# Simple-Temperature-Controller.net
KiCad netlist of a schematic drawn in EAGLE
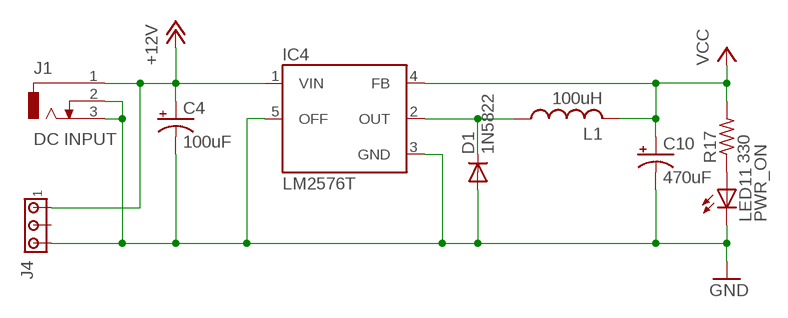
[diagram p0: schematic, sheet 1]
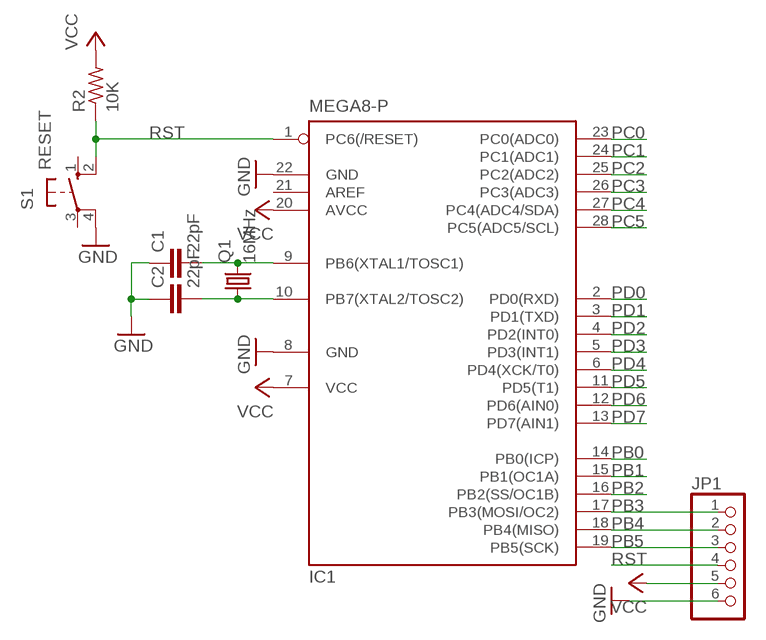
[diagram p1: schematic, sheet 2]
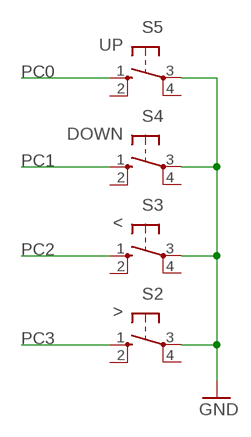
[diagram p2: schematic, sheet 3]
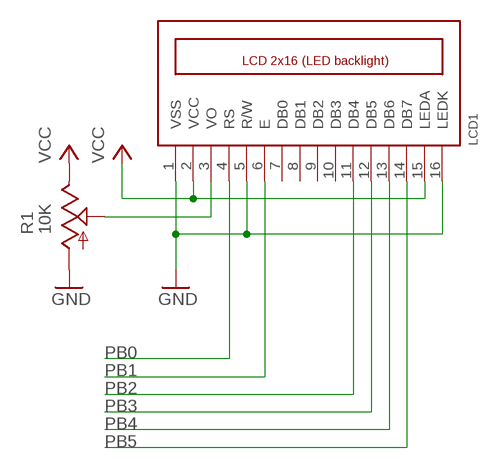
[diagram p3: schematic, sheet 4]
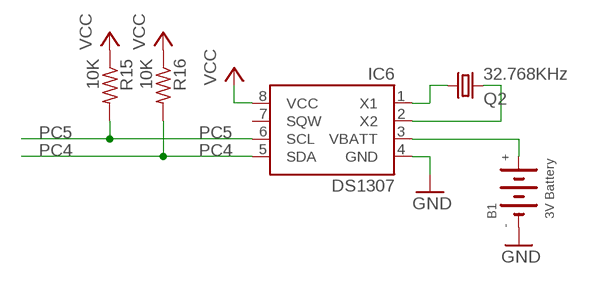
[diagram p4: schematic, sheet 5]
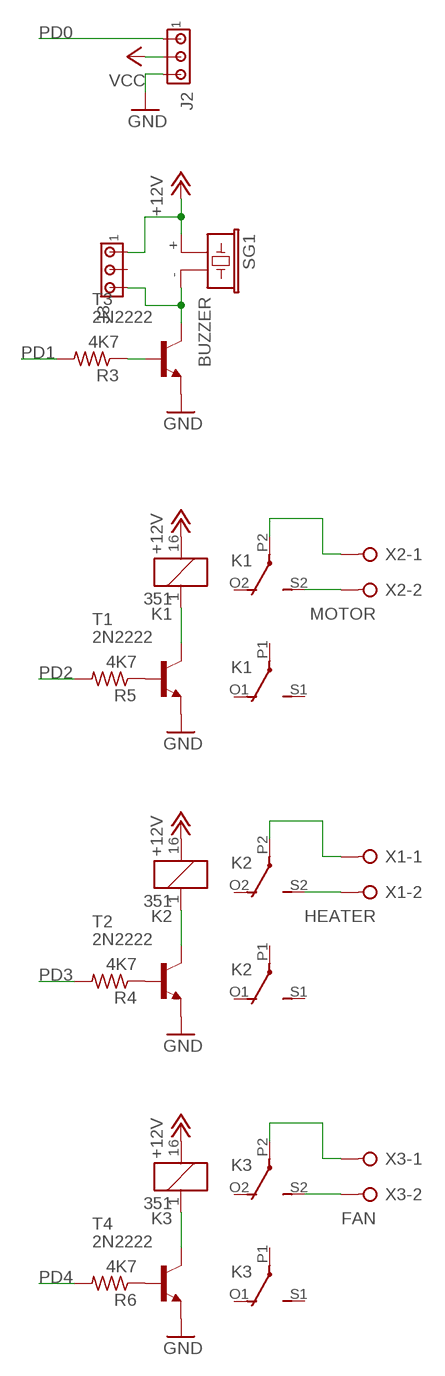
[diagram p5: schematic, sheet 6]

(export (version "E")
  (design (tool "Eeschema 10.0.6"))
  (components
    (comp (ref "C4")
      (value "100uF")
      (footprint "eagle-import:E2,5-6")
      (libsource (lib "eagle-import") (part "CPOL-USE2.5-6"))
    )
    (comp (ref "C10")
      (value "470uF")
      (footprint "eagle-import:E3,5-8")
      (libsource (lib "eagle-import") (part "CPOL-USE3.5-8"))
    )
    (comp (ref "D1")
      (value "1N5822")
      (footprint "eagle-import:DO201-15")
      (libsource (lib "eagle-import") (part "1N5400"))
    )
    (comp (ref "IC4")
      (value "LM2576T")
      (footprint "eagle-import:TO220-5")
      (libsource (lib "eagle-import") (part "LM2576T"))
    )
    (comp (ref "J1")
      (value "DC INPUT")
      (footprint "eagle-import:DCJ0202")
      (libsource (lib "eagle-import") (part "DCJ0202"))
    )
    (comp (ref "J4")
      (value "MTA03-100")
      (footprint "eagle-import:10X03MTA")
      (libsource (lib "eagle-import") (part "MTA03-100"))
    )
    (comp (ref "L1")
      (value "100uH")
      (footprint "eagle-import:TJ3-U2")
      (libsource (lib "eagle-import") (part "L-USTJ3-U2"))
    )
    (comp (ref "LED11")
      (value "PWR_ON")
      (footprint "eagle-import:LED3MM")
      (libsource (lib "eagle-import") (part "LED3MM"))
    )
    (comp (ref "R17")
      (value "330")
      (footprint "eagle-import:0207_10")
      (libsource (lib "eagle-import") (part "R-US_0207/10"))
    )
    (comp (ref "LCD1")
      (value "LCD-2X16")
      (footprint "eagle-import:LCD-2X16")
      (libsource (lib "eagle-import") (part "LCD-2X16"))
    )
    (comp (ref "R1")
      (value "10K")
      (footprint "eagle-import:POT_CA6V")
      (libsource (lib "eagle-import") (part "TRIMPOTCA6V"))
    )
    (comp (ref "J2")
      (value "MTA03-100")
      (footprint "eagle-import:10X03MTA")
      (libsource (lib "eagle-import") (part "MTA03-100"))
    )
    (comp (ref "J3")
      (value "MTA03-100")
      (footprint "eagle-import:10X03MTA")
      (libsource (lib "eagle-import") (part "MTA03-100"))
    )
    (comp (ref "K1")
      (value "351")
      (footprint "eagle-import:351")
      (libsource (lib "eagle-import") (part "351"))
    )
    (comp (ref "K2")
      (value "351")
      (footprint "eagle-import:351")
      (libsource (lib "eagle-import") (part "351"))
    )
    (comp (ref "K3")
      (value "351")
      (footprint "eagle-import:351")
      (libsource (lib "eagle-import") (part "351"))
    )
    (comp (ref "R3")
      (value "4K7")
      (footprint "eagle-import:0207_10")
      (libsource (lib "eagle-import") (part "R-US_0207/10"))
    )
    (comp (ref "R4")
      (value "4K7")
      (footprint "eagle-import:0207_10")
      (libsource (lib "eagle-import") (part "R-US_0207/10"))
    )
    (comp (ref "R5")
      (value "4K7")
      (footprint "eagle-import:0207_10")
      (libsource (lib "eagle-import") (part "R-US_0207/10"))
    )
    (comp (ref "R6")
      (value "4K7")
      (footprint "eagle-import:0207_10")
      (libsource (lib "eagle-import") (part "R-US_0207/10"))
    )
    (comp (ref "SG1")
      (value "BUZZER")
      (footprint "eagle-import:F_CM12P")
      (libsource (lib "eagle-import") (part "F/CM12P"))
    )
    (comp (ref "T1")
      (value "2N2222")
      (footprint "eagle-import:TO92-EBC-OVAL")
      (libsource (lib "eagle-import") (part "2N2222"))
    )
    (comp (ref "T2")
      (value "2N2222")
      (footprint "eagle-import:TO92-EBC-OVAL")
      (libsource (lib "eagle-import") (part "2N2222"))
    )
    (comp (ref "T3")
      (value "2N2222")
      (footprint "eagle-import:TO92-EBC-OVAL")
      (libsource (lib "eagle-import") (part "2N2222"))
    )
    (comp (ref "T4")
      (value "2N2222")
      (footprint "eagle-import:TO92-EBC-OVAL")
      (libsource (lib "eagle-import") (part "2N2222"))
    )
    (comp (ref "X1")
      (value "HEATER")
      (footprint "eagle-import:W237-132")
      (libsource (lib "eagle-import") (part "W237-02P"))
    )
    (comp (ref "X2")
      (value "MOTOR")
      (footprint "eagle-import:W237-132")
      (libsource (lib "eagle-import") (part "W237-02P"))
    )
    (comp (ref "X3")
      (value "FAN")
      (footprint "eagle-import:W237-132")
      (libsource (lib "eagle-import") (part "W237-02P"))
    )
    (comp (ref "C1")
      (value "22pF")
      (footprint "eagle-import:RESISTOR_C025-024X044")
      (libsource (lib "eagle-import") (part "CAPACITOR025-024X044"))
    )
    (comp (ref "C2")
      (value "22pF")
      (footprint "eagle-import:RESISTOR_C025-024X044")
      (libsource (lib "eagle-import") (part "CAPACITOR025-024X044"))
    )
    (comp (ref "IC1")
      (value "MEGA8-P")
      (footprint "eagle-import:DIL28-3")
      (libsource (lib "eagle-import") (part "MEGA8-P"))
    )
    (comp (ref "JP1")
      (value "PINHD-1X6")
      (footprint "eagle-import:1X06")
      (libsource (lib "eagle-import") (part "PINHD-1X6"))
    )
    (comp (ref "Q1")
      (value "16MHz")
      (footprint "eagle-import:HC49_S")
      (libsource (lib "eagle-import") (part "CRYSTALHC49S"))
    )
    (comp (ref "R2")
      (value "10K")
      (footprint "eagle-import:RESISTOR_0207_10")
      (libsource (lib "eagle-import") (part "RESISTOR0207/10"))
    )
    (comp (ref "S1")
      (value "RESET")
      (footprint "eagle-import:B3F-10XX")
      (fields (field (name "MPN") "B3F-1000"))
      (libsource (lib "eagle-import") (part "PUSH-BUTTON"))
    )
    (comp (ref "S2")
      (value ">")
      (footprint "eagle-import:B3F-10XX")
      (fields
        (field (name "MPN") "B3F-1000")
        (field (name "MPN_1") "B3F-1000")
        (field (name "OC_FARNELL") "176432")
        (field (name "OC_NEWARK") "36M3542")
      )
      (libsource (lib "eagle-import") (part "PUSH-BUTTON"))
    )
    (comp (ref "S3")
      (value "<")
      (footprint "eagle-import:B3F-10XX")
      (fields
        (field (name "MPN") "B3F-1000")
        (field (name "MPN_1") "B3F-1000")
        (field (name "OC_FARNELL") "176432")
        (field (name "OC_NEWARK") "36M3542")
      )
      (libsource (lib "eagle-import") (part "PUSH-BUTTON"))
    )
    (comp (ref "S4")
      (value "DOWN")
      (footprint "eagle-import:B3F-10XX")
      (fields
        (field (name "MPN") "B3F-1000")
        (field (name "MPN_1") "B3F-1000")
        (field (name "OC_FARNELL") "176432")
        (field (name "OC_NEWARK") "36M3542")
      )
      (libsource (lib "eagle-import") (part "PUSH-BUTTON"))
    )
    (comp (ref "S5")
      (value "UP")
      (footprint "eagle-import:B3F-10XX")
      (fields
        (field (name "MPN") "B3F-1000")
        (field (name "MPN_1") "B3F-1000")
        (field (name "OC_FARNELL") "176432")
        (field (name "OC_NEWARK") "36M3542")
      )
      (libsource (lib "eagle-import") (part "PUSH-BUTTON"))
    )
    (comp (ref "B1")
      (value "3V Battery")
      (footprint "eagle-import:CR2032")
      (libsource (lib "eagle-import") (part "BATTERYCR2032"))
    )
    (comp (ref "IC6")
      (value "DS1307")
      (footprint "eagle-import:DIP08")
      (libsource (lib "eagle-import") (part "DS1307"))
    )
    (comp (ref "Q2")
      (value "32.768KHz")
      (footprint "eagle-import:TC26H")
      (libsource (lib "eagle-import") (part "crystal_CRYSTALTC26H"))
    )
    (comp (ref "R15")
      (value "10K")
      (footprint "eagle-import:0207_10")
      (libsource (lib "eagle-import") (part "R-US_0207/10"))
    )
    (comp (ref "R16")
      (value "10K")
      (footprint "eagle-import:0207_10")
      (libsource (lib "eagle-import") (part "R-US_0207/10"))
    )
  )
  (nets
    (net (code "1") (name "+12V") (class "Default")
      (node (ref "C4") (pin "+") (pinfunction "+_+") (pintype "passive"))
      (node (ref "IC4") (pin "1") (pinfunction "VIN_1") (pintype "power_in"))
      (node (ref "J1") (pin "1") (pinfunction "1_1") (pintype "passive"))
      (node (ref "J3") (pin "1") (pinfunction "1_1") (pintype "passive"))
      (node (ref "J4") (pin "1") (pinfunction "1_1") (pintype "passive"))
      (node (ref "K1") (pin "16") (pinfunction "2_16") (pintype "passive"))
      (node (ref "K2") (pin "16") (pinfunction "2_16") (pintype "passive"))
      (node (ref "K3") (pin "16") (pinfunction "2_16") (pintype "passive"))
      (node (ref "SG1") (pin "+") (pinfunction "1_+") (pintype "passive"))
    )
    (net (code "2") (name "GND") (class "Default")
      (node (ref "B1") (pin "-") (pinfunction "-_-") (pintype "passive"))
      (node (ref "C1") (pin "1") (pinfunction "1_1") (pintype "passive"))
      (node (ref "C10") (pin "-") (pinfunction "-_-") (pintype "passive"))
      (node (ref "C2") (pin "1") (pinfunction "1_1") (pintype "passive"))
      (node (ref "C4") (pin "-") (pinfunction "-_-") (pintype "passive"))
      (node (ref "D1") (pin "A") (pinfunction "A_A") (pintype "passive"))
      (node (ref "IC1") (pin "22") (pinfunction "GND_22") (pintype "power_in"))
      (node (ref "IC1") (pin "8") (pinfunction "GND_8") (pintype "power_in"))
      (node (ref "IC4") (pin "3") (pinfunction "GND_3") (pintype "power_in"))
      (node (ref "IC4") (pin "5") (pinfunction "OFF_5") (pintype "input"))
      (node (ref "IC6") (pin "4") (pinfunction "GND_4") (pintype "bidirectional"))
      (node (ref "J1") (pin "2") (pinfunction "2_2") (pintype "passive"))
      (node (ref "J1") (pin "3") (pinfunction "3_3") (pintype "passive"))
      (node (ref "J2") (pin "3") (pinfunction "3_3") (pintype "passive"))
      (node (ref "J4") (pin "3") (pinfunction "3_3") (pintype "passive"))
      (node (ref "JP1") (pin "6") (pinfunction "6_6") (pintype "passive"))
      (node (ref "LCD1") (pin "1") (pinfunction "VSS_1") (pintype "power_in"))
      (node (ref "LCD1") (pin "16") (pinfunction "LEDK_16") (pintype "passive"))
      (node (ref "LCD1") (pin "5") (pinfunction "R/W_5") (pintype "input"))
      (node (ref "LED11") (pin "K") (pinfunction "C_K") (pintype "passive"))
      (node (ref "R1") (pin "A") (pinfunction "A_A") (pintype "passive"))
      (node (ref "S1") (pin "4") (pinfunction "P1_4") (pintype "passive"))
      (node (ref "S2") (pin "3") (pinfunction "P_3") (pintype "passive"))
      (node (ref "S3") (pin "3") (pinfunction "P_3") (pintype "passive"))
      (node (ref "S4") (pin "3") (pinfunction "P_3") (pintype "passive"))
      (node (ref "S5") (pin "3") (pinfunction "P_3") (pintype "passive"))
      (node (ref "T1") (pin "E") (pinfunction "E_E") (pintype "passive"))
      (node (ref "T2") (pin "E") (pinfunction "E_E") (pintype "passive"))
      (node (ref "T3") (pin "E") (pinfunction "E_E") (pintype "passive"))
      (node (ref "T4") (pin "E") (pinfunction "E_E") (pintype "passive"))
    )
    (net (code "3") (name "Net-(IC1-PB6(XTAL1{slash}TOSC1))") (class "Default")
      (node (ref "C1") (pin "2") (pinfunction "2_2") (pintype "passive"))
      (node (ref "IC1") (pin "9") (pinfunction "PB6(XTAL1/TOSC1)_9") (pintype "bidirectional"))
      (node (ref "Q1") (pin "2") (pinfunction "2_2") (pintype "passive"))
    )
    (net (code "4") (name "Net-(IC1-PB7(XTAL2{slash}TOSC2))") (class "Default")
      (node (ref "C2") (pin "2") (pinfunction "2_2") (pintype "passive"))
      (node (ref "IC1") (pin "10") (pinfunction "PB7(XTAL2/TOSC2)_10") (pintype "bidirectional"))
      (node (ref "Q1") (pin "1") (pinfunction "1_1") (pintype "passive"))
    )
    (net (code "5") (name "Net-(IC4-OUT)") (class "Default")
      (node (ref "D1") (pin "C") (pinfunction "C_C") (pintype "passive"))
      (node (ref "IC4") (pin "2") (pinfunction "OUT_2") (pintype "output"))
      (node (ref "L1") (pin "1") (pinfunction "1_1") (pintype "passive"))
    )
    (net (code "6") (name "Net-(IC6-VBATT)") (class "Default")
      (node (ref "B1") (pin "+") (pinfunction "+_+") (pintype "passive"))
      (node (ref "IC6") (pin "3") (pinfunction "VBATT_3") (pintype "bidirectional"))
    )
    (net (code "7") (name "Net-(IC6-X1)") (class "Default")
      (node (ref "IC6") (pin "1") (pinfunction "X1_1") (pintype "bidirectional"))
      (node (ref "Q2") (pin "1") (pinfunction "1_1") (pintype "passive"))
    )
    (net (code "8") (name "Net-(IC6-X2)") (class "Default")
      (node (ref "IC6") (pin "2") (pinfunction "X2_2") (pintype "bidirectional"))
      (node (ref "Q2") (pin "2") (pinfunction "2_2") (pintype "passive"))
    )
    (net (code "9") (name "Net-(K1-Pad1)") (class "Default")
      (node (ref "K1") (pin "1") (pinfunction "1_1") (pintype "passive"))
      (node (ref "T1") (pin "C") (pinfunction "C_C") (pintype "passive"))
    )
    (net (code "10") (name "Net-(K1C-P)") (class "Default")
      (node (ref "K1") (pin "P2") (pinfunction "P_P2") (pintype "passive"))
      (node (ref "X2") (pin "1") (pinfunction "KL_1") (pintype "passive"))
    )
    (net (code "11") (name "Net-(K1C-S)") (class "Default")
      (node (ref "K1") (pin "S2") (pinfunction "S_S2") (pintype "passive"))
      (node (ref "X2") (pin "2") (pinfunction "KL_2") (pintype "passive"))
    )
    (net (code "12") (name "Net-(K2-Pad1)") (class "Default")
      (node (ref "K2") (pin "1") (pinfunction "1_1") (pintype "passive"))
      (node (ref "T2") (pin "C") (pinfunction "C_C") (pintype "passive"))
    )
    (net (code "13") (name "Net-(K2C-P)") (class "Default")
      (node (ref "K2") (pin "P2") (pinfunction "P_P2") (pintype "passive"))
      (node (ref "X1") (pin "1") (pinfunction "KL_1") (pintype "passive"))
    )
    (net (code "14") (name "Net-(K2C-S)") (class "Default")
      (node (ref "K2") (pin "S2") (pinfunction "S_S2") (pintype "passive"))
      (node (ref "X1") (pin "2") (pinfunction "KL_2") (pintype "passive"))
    )
    (net (code "15") (name "Net-(K3-Pad1)") (class "Default")
      (node (ref "K3") (pin "1") (pinfunction "1_1") (pintype "passive"))
      (node (ref "T4") (pin "C") (pinfunction "C_C") (pintype "passive"))
    )
    (net (code "16") (name "Net-(K3C-P)") (class "Default")
      (node (ref "K3") (pin "P2") (pinfunction "P_P2") (pintype "passive"))
      (node (ref "X3") (pin "1") (pinfunction "KL_1") (pintype "passive"))
    )
    (net (code "17") (name "Net-(K3C-S)") (class "Default")
      (node (ref "K3") (pin "S2") (pinfunction "S_S2") (pintype "passive"))
      (node (ref "X3") (pin "2") (pinfunction "KL_2") (pintype "passive"))
    )
    (net (code "18") (name "Net-(LCD1-VO)") (class "Default")
      (node (ref "LCD1") (pin "3") (pinfunction "VO_3") (pintype "input"))
      (node (ref "R1") (pin "S") (pinfunction "S_S") (pintype "passive"))
    )
    (net (code "19") (name "Net-(LED11-PadA)") (class "Default")
      (node (ref "LED11") (pin "A") (pinfunction "A_A") (pintype "passive"))
      (node (ref "R17") (pin "1") (pinfunction "1_1") (pintype "passive"))
    )
    (net (code "20") (name "Net-(R3-Pad1)") (class "Default")
      (node (ref "R3") (pin "1") (pinfunction "1_1") (pintype "passive"))
      (node (ref "T3") (pin "B") (pinfunction "B_B") (pintype "passive"))
    )
    (net (code "21") (name "Net-(R4-Pad1)") (class "Default")
      (node (ref "R4") (pin "1") (pinfunction "1_1") (pintype "passive"))
      (node (ref "T2") (pin "B") (pinfunction "B_B") (pintype "passive"))
    )
    (net (code "22") (name "Net-(R5-Pad1)") (class "Default")
      (node (ref "R5") (pin "1") (pinfunction "1_1") (pintype "passive"))
      (node (ref "T1") (pin "B") (pinfunction "B_B") (pintype "passive"))
    )
    (net (code "23") (name "Net-(R6-Pad1)") (class "Default")
      (node (ref "R6") (pin "1") (pinfunction "1_1") (pintype "passive"))
      (node (ref "T4") (pin "B") (pinfunction "B_B") (pintype "passive"))
    )
    (net (code "24") (name "Net-(SG1-2)") (class "Default")
      (node (ref "J3") (pin "3") (pinfunction "3_3") (pintype "passive"))
      (node (ref "SG1") (pin "-") (pinfunction "2_-") (pintype "passive"))
      (node (ref "T3") (pin "C") (pinfunction "C_C") (pintype "passive"))
    )
    (net (code "25") (name "PB0") (class "Default")
      (node (ref "IC1") (pin "14") (pinfunction "PB0(ICP)_14") (pintype "bidirectional"))
      (node (ref "LCD1") (pin "4") (pinfunction "RS_4") (pintype "input"))
    )
    (net (code "26") (name "PB1") (class "Default")
      (node (ref "IC1") (pin "15") (pinfunction "PB1(OC1A)_15") (pintype "bidirectional"))
      (node (ref "LCD1") (pin "6") (pinfunction "E_6") (pintype "input"))
    )
    (net (code "27") (name "PB2") (class "Default")
      (node (ref "IC1") (pin "16") (pinfunction "PB2(SS/OC1B)_16") (pintype "bidirectional"))
      (node (ref "LCD1") (pin "11") (pinfunction "DB4_11") (pintype "bidirectional"))
    )
    (net (code "28") (name "PB3") (class "Default")
      (node (ref "IC1") (pin "17") (pinfunction "PB3(MOSI/OC2)_17") (pintype "bidirectional"))
      (node (ref "JP1") (pin "1") (pinfunction "1_1") (pintype "passive"))
      (node (ref "LCD1") (pin "12") (pinfunction "DB5_12") (pintype "bidirectional"))
    )
    (net (code "29") (name "PB4") (class "Default")
      (node (ref "IC1") (pin "18") (pinfunction "PB4(MISO)_18") (pintype "bidirectional"))
      (node (ref "JP1") (pin "2") (pinfunction "2_2") (pintype "passive"))
      (node (ref "LCD1") (pin "13") (pinfunction "DB6_13") (pintype "bidirectional"))
    )
    (net (code "30") (name "PB5") (class "Default")
      (node (ref "IC1") (pin "19") (pinfunction "PB5(SCK)_19") (pintype "bidirectional"))
      (node (ref "JP1") (pin "3") (pinfunction "3_3") (pintype "passive"))
      (node (ref "LCD1") (pin "14") (pinfunction "DB7_14") (pintype "bidirectional"))
    )
    (net (code "31") (name "PC0") (class "Default")
      (node (ref "IC1") (pin "23") (pinfunction "PC0(ADC0)_23") (pintype "bidirectional"))
      (node (ref "S5") (pin "1") (pinfunction "S_1") (pintype "passive"))
    )
    (net (code "32") (name "PC1") (class "Default")
      (node (ref "IC1") (pin "24") (pinfunction "PC1(ADC1)_24") (pintype "bidirectional"))
      (node (ref "S4") (pin "1") (pinfunction "S_1") (pintype "passive"))
    )
    (net (code "33") (name "PC2") (class "Default")
      (node (ref "IC1") (pin "25") (pinfunction "PC2(ADC2)_25") (pintype "bidirectional"))
      (node (ref "S3") (pin "1") (pinfunction "S_1") (pintype "passive"))
    )
    (net (code "34") (name "PC3") (class "Default")
      (node (ref "IC1") (pin "26") (pinfunction "PC3(ADC3)_26") (pintype "bidirectional"))
      (node (ref "S2") (pin "1") (pinfunction "S_1") (pintype "passive"))
    )
    (net (code "35") (name "PC4") (class "Default")
      (node (ref "IC1") (pin "27") (pinfunction "PC4(ADC4/SDA)_27") (pintype "bidirectional"))
      (node (ref "IC6") (pin "5") (pinfunction "SDA_5") (pintype "bidirectional"))
      (node (ref "R16") (pin "2") (pinfunction "2_2") (pintype "passive"))
    )
    (net (code "36") (name "PC5") (class "Default")
      (node (ref "IC1") (pin "28") (pinfunction "PC5(ADC5/SCL)_28") (pintype "bidirectional"))
      (node (ref "IC6") (pin "6") (pinfunction "SCL_6") (pintype "bidirectional"))
      (node (ref "R15") (pin "2") (pinfunction "2_2") (pintype "passive"))
    )
    (net (code "37") (name "PD0") (class "Default")
      (node (ref "IC1") (pin "2") (pinfunction "PD0(RXD)_2") (pintype "bidirectional"))
      (node (ref "J2") (pin "1") (pinfunction "1_1") (pintype "passive"))
    )
    (net (code "38") (name "PD1") (class "Default")
      (node (ref "IC1") (pin "3") (pinfunction "PD1(TXD)_3") (pintype "bidirectional"))
      (node (ref "R3") (pin "2") (pinfunction "2_2") (pintype "passive"))
    )
    (net (code "39") (name "PD2") (class "Default")
      (node (ref "IC1") (pin "4") (pinfunction "PD2(INT0)_4") (pintype "bidirectional"))
      (node (ref "R5") (pin "2") (pinfunction "2_2") (pintype "passive"))
    )
    (net (code "40") (name "PD3") (class "Default")
      (node (ref "IC1") (pin "5") (pinfunction "PD3(INT1)_5") (pintype "bidirectional"))
      (node (ref "R4") (pin "2") (pinfunction "2_2") (pintype "passive"))
    )
    (net (code "41") (name "PD4") (class "Default")
      (node (ref "IC1") (pin "6") (pinfunction "PD4(XCK/T0)_6") (pintype "bidirectional"))
      (node (ref "R6") (pin "2") (pinfunction "2_2") (pintype "passive"))
    )
    (net (code "42") (name "PD5") (class "Default")
      (node (ref "IC1") (pin "11") (pinfunction "PD5(T1)_11") (pintype "bidirectional"))
    )
    (net (code "43") (name "PD6") (class "Default")
      (node (ref "IC1") (pin "12") (pinfunction "PD6(AIN0)_12") (pintype "bidirectional"))
    )
    (net (code "44") (name "PD7") (class "Default")
      (node (ref "IC1") (pin "13") (pinfunction "PD7(AIN1)_13") (pintype "bidirectional"))
    )
    (net (code "45") (name "RST") (class "Default")
      (node (ref "IC1") (pin "1") (pinfunction "PC6(/RESET)_1") (pintype "bidirectional"))
      (node (ref "JP1") (pin "4") (pinfunction "4_4") (pintype "passive"))
      (node (ref "R2") (pin "1") (pinfunction "1_1") (pintype "passive"))
      (node (ref "S1") (pin "2") (pinfunction "S1_2") (pintype "passive"))
    )
    (net (code "46") (name "VCC") (class "Default")
      (node (ref "C10") (pin "+") (pinfunction "+_+") (pintype "passive"))
      (node (ref "IC1") (pin "20") (pinfunction "AVCC_20") (pintype "power_in"))
      (node (ref "IC1") (pin "7") (pinfunction "VCC_7") (pintype "power_in"))
      (node (ref "IC4") (pin "4") (pinfunction "FB_4") (pintype "input"))
      (node (ref "IC6") (pin "8") (pinfunction "VCC_8") (pintype "bidirectional"))
      (node (ref "J2") (pin "2") (pinfunction "2_2") (pintype "passive"))
      (node (ref "JP1") (pin "5") (pinfunction "5_5") (pintype "passive"))
      (node (ref "L1") (pin "2") (pinfunction "2_2") (pintype "passive"))
      (node (ref "LCD1") (pin "15") (pinfunction "LEDA_15") (pintype "passive"))
      (node (ref "LCD1") (pin "2") (pinfunction "VCC_2") (pintype "power_in"))
      (node (ref "R1") (pin "E") (pinfunction "E_E") (pintype "passive"))
      (node (ref "R15") (pin "1") (pinfunction "1_1") (pintype "passive"))
      (node (ref "R16") (pin "1") (pinfunction "1_1") (pintype "passive"))
      (node (ref "R17") (pin "2") (pinfunction "2_2") (pintype "passive"))
      (node (ref "R2") (pin "2") (pinfunction "2_2") (pintype "passive"))
    )
    (net (code "47") (name "unconnected-(IC1-AREF-Pad21)") (class "Default")
      (node (ref "IC1") (pin "21") (pinfunction "AREF_21") (pintype "passive"))
    )
    (net (code "48") (name "unconnected-(IC6-SQW-Pad7)") (class "Default")
      (node (ref "IC6") (pin "7") (pinfunction "SQW_7") (pintype "bidirectional"))
    )
    (net (code "49") (name "unconnected-(J3-Pad2)") (class "Default")
      (node (ref "J3") (pin "2") (pinfunction "2_2") (pintype "passive"))
    )
    (net (code "50") (name "unconnected-(J4-Pad2)") (class "Default")
      (node (ref "J4") (pin "2") (pinfunction "2_2") (pintype "passive"))
    )
    (net (code "51") (name "unconnected-(K1B-O-PadO1)") (class "Default")
      (node (ref "K1") (pin "O1") (pinfunction "O_O1") (pintype "passive"))
    )
    (net (code "52") (name "unconnected-(K1B-P-PadP1)") (class "Default")
      (node (ref "K1") (pin "P1") (pinfunction "P_P1") (pintype "passive"))
    )
    (net (code "53") (name "unconnected-(K1B-S-PadS1)") (class "Default")
      (node (ref "K1") (pin "S1") (pinfunction "S_S1") (pintype "passive"))
    )
    (net (code "54") (name "unconnected-(K1C-O-PadO2)") (class "Default")
      (node (ref "K1") (pin "O2") (pinfunction "O_O2") (pintype "passive"))
    )
    (net (code "55") (name "unconnected-(K2B-O-PadO1)") (class "Default")
      (node (ref "K2") (pin "O1") (pinfunction "O_O1") (pintype "passive"))
    )
    (net (code "56") (name "unconnected-(K2B-P-PadP1)") (class "Default")
      (node (ref "K2") (pin "P1") (pinfunction "P_P1") (pintype "passive"))
    )
    (net (code "57") (name "unconnected-(K2B-S-PadS1)") (class "Default")
      (node (ref "K2") (pin "S1") (pinfunction "S_S1") (pintype "passive"))
    )
    (net (code "58") (name "unconnected-(K2C-O-PadO2)") (class "Default")
      (node (ref "K2") (pin "O2") (pinfunction "O_O2") (pintype "passive"))
    )
    (net (code "59") (name "unconnected-(K3B-O-PadO1)") (class "Default")
      (node (ref "K3") (pin "O1") (pinfunction "O_O1") (pintype "passive"))
    )
    (net (code "60") (name "unconnected-(K3B-P-PadP1)") (class "Default")
      (node (ref "K3") (pin "P1") (pinfunction "P_P1") (pintype "passive"))
    )
    (net (code "61") (name "unconnected-(K3B-S-PadS1)") (class "Default")
      (node (ref "K3") (pin "S1") (pinfunction "S_S1") (pintype "passive"))
    )
    (net (code "62") (name "unconnected-(K3C-O-PadO2)") (class "Default")
      (node (ref "K3") (pin "O2") (pinfunction "O_O2") (pintype "passive"))
    )
    (net (code "63") (name "unconnected-(LCD1-DB0-Pad7)") (class "Default")
      (node (ref "LCD1") (pin "7") (pinfunction "DB0_7") (pintype "bidirectional"))
    )
    (net (code "64") (name "unconnected-(LCD1-DB1-Pad8)") (class "Default")
      (node (ref "LCD1") (pin "8") (pinfunction "DB1_8") (pintype "bidirectional"))
    )
    (net (code "65") (name "unconnected-(LCD1-DB2-Pad9)") (class "Default")
      (node (ref "LCD1") (pin "9") (pinfunction "DB2_9") (pintype "bidirectional"))
    )
    (net (code "66") (name "unconnected-(LCD1-DB3-Pad10)") (class "Default")
      (node (ref "LCD1") (pin "10") (pinfunction "DB3_10") (pintype "bidirectional"))
    )
    (net (code "67") (name "unconnected-(S1-P-Pad3)") (class "Default")
      (node (ref "S1") (pin "3") (pinfunction "P_3") (pintype "passive"))
    )
    (net (code "68") (name "unconnected-(S1-S-Pad1)") (class "Default")
      (node (ref "S1") (pin "1") (pinfunction "S_1") (pintype "passive"))
    )
    (net (code "69") (name "unconnected-(S2-P1-Pad4)") (class "Default")
      (node (ref "S2") (pin "4") (pinfunction "P1_4") (pintype "passive"))
    )
    (net (code "70") (name "unconnected-(S2-S1-Pad2)") (class "Default")
      (node (ref "S2") (pin "2") (pinfunction "S1_2") (pintype "passive"))
    )
    (net (code "71") (name "unconnected-(S3-P1-Pad4)") (class "Default")
      (node (ref "S3") (pin "4") (pinfunction "P1_4") (pintype "passive"))
    )
    (net (code "72") (name "unconnected-(S3-S1-Pad2)") (class "Default")
      (node (ref "S3") (pin "2") (pinfunction "S1_2") (pintype "passive"))
    )
    (net (code "73") (name "unconnected-(S4-P1-Pad4)") (class "Default")
      (node (ref "S4") (pin "4") (pinfunction "P1_4") (pintype "passive"))
    )
    (net (code "74") (name "unconnected-(S4-S1-Pad2)") (class "Default")
      (node (ref "S4") (pin "2") (pinfunction "S1_2") (pintype "passive"))
    )
    (net (code "75") (name "unconnected-(S5-P1-Pad4)") (class "Default")
      (node (ref "S5") (pin "4") (pinfunction "P1_4") (pintype "passive"))
    )
    (net (code "76") (name "unconnected-(S5-S1-Pad2)") (class "Default")
      (node (ref "S5") (pin "2") (pinfunction "S1_2") (pintype "passive"))
    )
  )
)
